# SHIELD_TEST_DISP.net
KiCad netlist of a schematic drawn in EAGLE
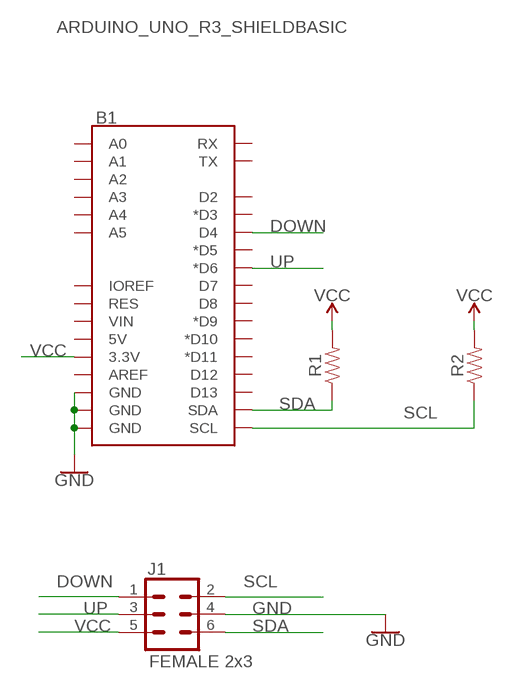
[diagram p0: schematic, sheet 1]

(export (version "E")
  (design (tool "Eeschema 10.0.6"))
  (components
    (comp (ref "B1")
      (value "ARDUINO_UNO_R3_SHIELDBASIC")
      (footprint "eagle-import:UNO_R3_SHIELD")
      (libsource (lib "eagle-import") (part "ARDUINO_UNO_R3_SHIELDBASIC"))
    )
    (comp (ref "J1")
      (value "FEMALE 2x3")
      (footprint "eagle-import:2X3")
      (libsource (lib "eagle-import") (part "CONN_03X2FEMALE"))
    )
    (comp (ref "R1")
      (value "RESISTOR0805")
      (footprint "eagle-import:0805")
      (libsource (lib "eagle-import") (part "RESISTOR0805"))
    )
    (comp (ref "R2")
      (value "RESISTOR0805")
      (footprint "eagle-import:0805")
      (libsource (lib "eagle-import") (part "RESISTOR0805"))
    )
  )
  (nets
    (net (code "1") (name "/DOWN") (class "Default")
      (node (ref "B1") (pin "D4") (pinfunction "D4_D4") (pintype "bidirectional"))
      (node (ref "J1") (pin "1") (pinfunction "1_1") (pintype "bidirectional"))
    )
    (net (code "2") (name "/SCL") (class "Default")
      (node (ref "B1") (pin "SCL") (pinfunction "SCL_SCL") (pintype "bidirectional"))
      (node (ref "J1") (pin "2") (pinfunction "2_2") (pintype "bidirectional"))
      (node (ref "R2") (pin "1") (pinfunction "1_1") (pintype "passive"))
    )
    (net (code "3") (name "/SDA") (class "Default")
      (node (ref "B1") (pin "SDA") (pinfunction "SDA_SDA") (pintype "bidirectional"))
      (node (ref "J1") (pin "6") (pinfunction "6_6") (pintype "bidirectional"))
      (node (ref "R1") (pin "1") (pinfunction "1_1") (pintype "passive"))
    )
    (net (code "4") (name "/UP") (class "Default")
      (node (ref "B1") (pin "D6") (pinfunction "*D6_D6") (pintype "bidirectional"))
      (node (ref "J1") (pin "3") (pinfunction "3_3") (pintype "bidirectional"))
    )
    (net (code "5") (name "GND") (class "Default")
      (node (ref "B1") (pin "GND@0") (pinfunction "GND_GND@0") (pintype "bidirectional"))
      (node (ref "B1") (pin "GND@1") (pinfunction "GND_GND@1") (pintype "bidirectional"))
      (node (ref "B1") (pin "GND@2") (pinfunction "GND_GND@2") (pintype "bidirectional"))
      (node (ref "J1") (pin "4") (pinfunction "4_4") (pintype "bidirectional"))
    )
    (net (code "6") (name "VCC") (class "Default")
      (node (ref "B1") (pin "3.3V") (pinfunction "3.3V_3.3V") (pintype "bidirectional"))
      (node (ref "J1") (pin "5") (pinfunction "5_5") (pintype "bidirectional"))
      (node (ref "R1") (pin "2") (pinfunction "2_2") (pintype "passive"))
      (node (ref "R2") (pin "2") (pinfunction "2_2") (pintype "passive"))
    )
    (net (code "7") (name "unconnected-(B1-*D3-PadD3)") (class "Default")
      (node (ref "B1") (pin "D3") (pinfunction "*D3_D3") (pintype "bidirectional"))
    )
    (net (code "8") (name "unconnected-(B1-*D5-PadD5)") (class "Default")
      (node (ref "B1") (pin "D5") (pinfunction "*D5_D5") (pintype "bidirectional"))
    )
    (net (code "9") (name "unconnected-(B1-*D9-PadD9)") (class "Default")
      (node (ref "B1") (pin "D9") (pinfunction "*D9_D9") (pintype "bidirectional"))
    )
    (net (code "10") (name "unconnected-(B1-*D10-PadD10)") (class "Default")
      (node (ref "B1") (pin "D10") (pinfunction "*D10_D10") (pintype "bidirectional"))
    )
    (net (code "11") (name "unconnected-(B1-*D11-PadD11)") (class "Default")
      (node (ref "B1") (pin "D11") (pinfunction "*D11_D11") (pintype "bidirectional"))
    )
    (net (code "12") (name "unconnected-(B1-Pad5V)") (class "Default")
      (node (ref "B1") (pin "5V") (pinfunction "5V_5V") (pintype "bidirectional"))
    )
    (net (code "13") (name "unconnected-(B1-PadA0)") (class "Default")
      (node (ref "B1") (pin "A0") (pinfunction "A0_A0") (pintype "bidirectional"))
    )
    (net (code "14") (name "unconnected-(B1-PadA1)") (class "Default")
      (node (ref "B1") (pin "A1") (pinfunction "A1_A1") (pintype "bidirectional"))
    )
    (net (code "15") (name "unconnected-(B1-PadA2)") (class "Default")
      (node (ref "B1") (pin "A2") (pinfunction "A2_A2") (pintype "bidirectional"))
    )
    (net (code "16") (name "unconnected-(B1-PadA3)") (class "Default")
      (node (ref "B1") (pin "A3") (pinfunction "A3_A3") (pintype "bidirectional"))
    )
    (net (code "17") (name "unconnected-(B1-PadA4)") (class "Default")
      (node (ref "B1") (pin "A4") (pinfunction "A4_A4") (pintype "bidirectional"))
    )
    (net (code "18") (name "unconnected-(B1-PadA5)") (class "Default")
      (node (ref "B1") (pin "A5") (pinfunction "A5_A5") (pintype "bidirectional"))
    )
    (net (code "19") (name "unconnected-(B1-PadAREF)") (class "Default")
      (node (ref "B1") (pin "AREF") (pinfunction "AREF_AREF") (pintype "bidirectional"))
    )
    (net (code "20") (name "unconnected-(B1-PadD2)") (class "Default")
      (node (ref "B1") (pin "D2") (pinfunction "D2_D2") (pintype "bidirectional"))
    )
    (net (code "21") (name "unconnected-(B1-PadD7)") (class "Default")
      (node (ref "B1") (pin "D7") (pinfunction "D7_D7") (pintype "bidirectional"))
    )
    (net (code "22") (name "unconnected-(B1-PadD8)") (class "Default")
      (node (ref "B1") (pin "D8") (pinfunction "D8_D8") (pintype "bidirectional"))
    )
    (net (code "23") (name "unconnected-(B1-PadD12)") (class "Default")
      (node (ref "B1") (pin "D12") (pinfunction "D12_D12") (pintype "bidirectional"))
    )
    (net (code "24") (name "unconnected-(B1-PadD13)") (class "Default")
      (node (ref "B1") (pin "D13") (pinfunction "D13_D13") (pintype "bidirectional"))
    )
    (net (code "25") (name "unconnected-(B1-PadIOREF)") (class "Default")
      (node (ref "B1") (pin "IOREF") (pinfunction "IOREF_IOREF") (pintype "bidirectional"))
    )
    (net (code "26") (name "unconnected-(B1-PadRES)") (class "Default")
      (node (ref "B1") (pin "RES") (pinfunction "RES_RES") (pintype "bidirectional"))
    )
    (net (code "27") (name "unconnected-(B1-PadRX)") (class "Default")
      (node (ref "B1") (pin "RX") (pinfunction "RX_RX") (pintype "bidirectional"))
    )
    (net (code "28") (name "unconnected-(B1-PadTX)") (class "Default")
      (node (ref "B1") (pin "TX") (pinfunction "TX_TX") (pintype "bidirectional"))
    )
    (net (code "29") (name "unconnected-(B1-PadVIN)") (class "Default")
      (node (ref "B1") (pin "VIN") (pinfunction "VIN_VIN") (pintype "bidirectional"))
    )
  )
)
